# 03_TOF.net
KiCad netlist of a schematic drawn in Altium Designer
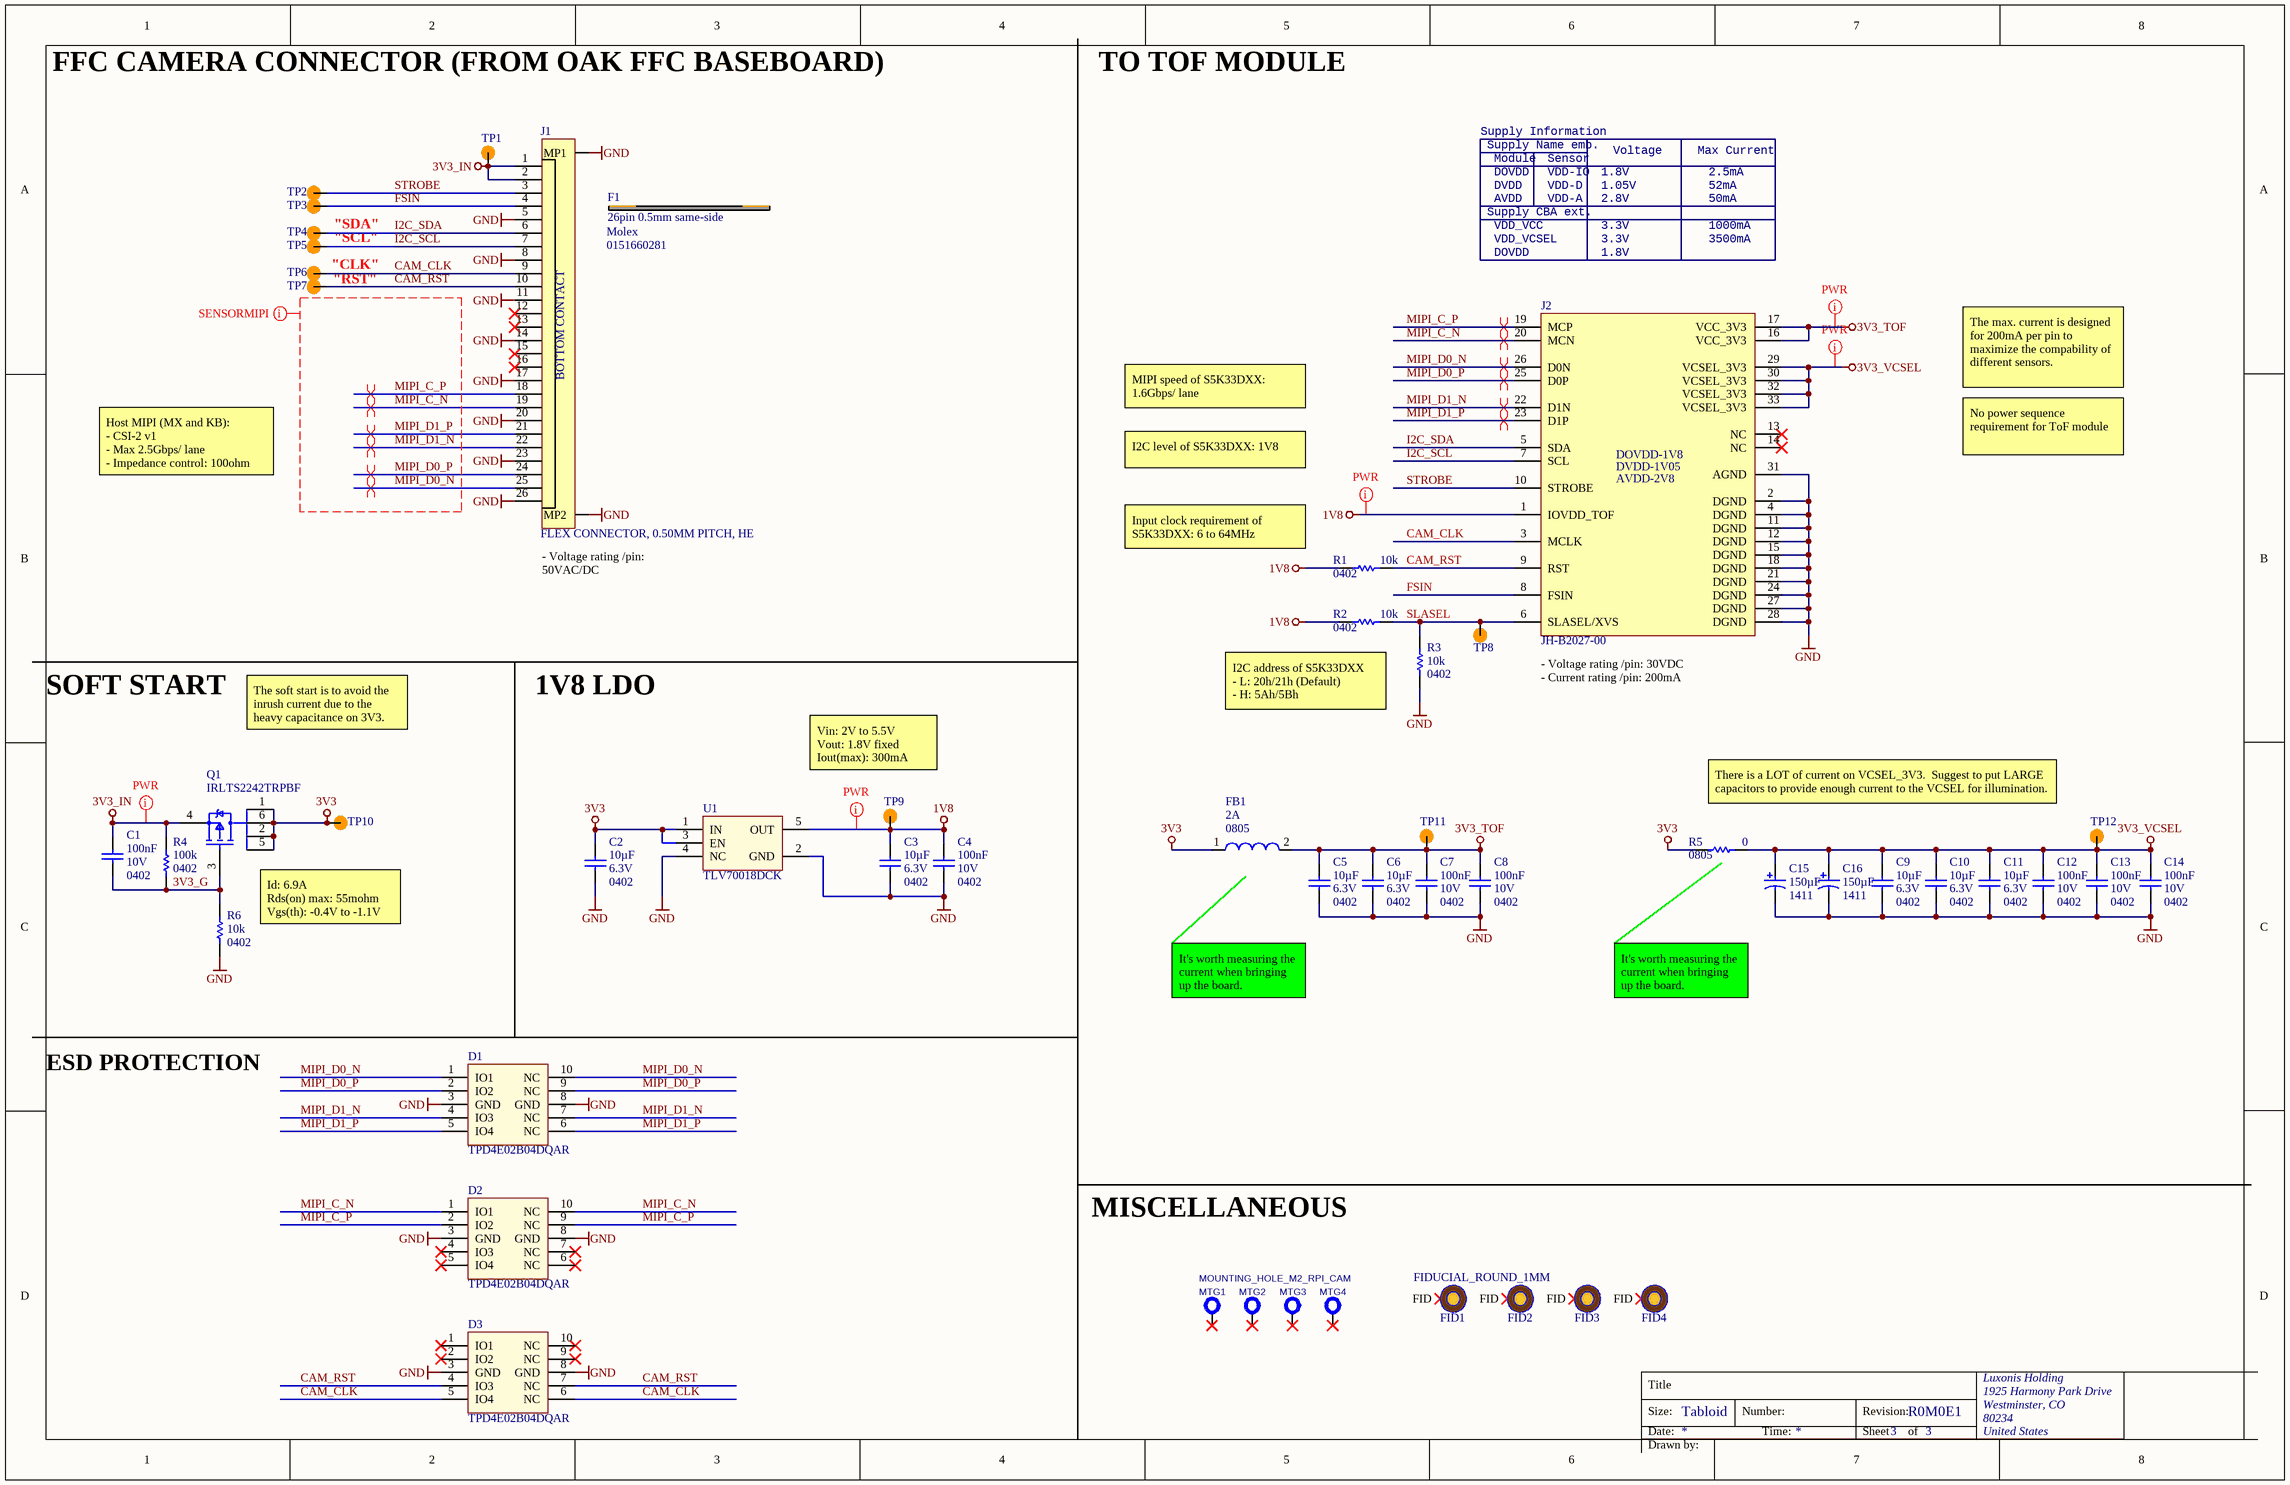
[diagram p0: 03_TOF.SchDoc]

(export (version "E")
  (design (tool "Eeschema 10.0.6"))
  (components
    (comp (ref "C1")
      (value "100nF")
      (footprint "CAPC0402(1005)70_N")
      (description "CAP CER 0.1UF 10V X7R 0402 5%")
      (fields
        (field (name "VOLTAGE RATING") "10V")
        (field (name "TOLERANCE") "5%")
        (field (name "CASE/PACKAGE") "0402")
        (field (name "Comment") "GRM155R71A104JA01D")
      )
      (libsource (lib "Luxonis LLC") (part "GRM188R61C475KAAJD"))
    )
    (comp (ref "C2")
      (value "10µF")
      (footprint "CAPC0402(1005)70_L")
      (description "CAP CER 10UF 6.3V X5R 0402 20%")
      (fields
        (field (name "CASE/PACKAGE") "0402")
        (field (name "TOLERANCE") "20%")
        (field (name "VOLTAGE RATING") "6.3V")
        (field (name "Comment") "GRM155R60J106ME15D")
      )
      (libsource (lib "Luxonis LLC") (part "LLL153C70G474ME17E"))
    )
    (comp (ref "C3")
      (value "10µF")
      (footprint "CAPC0402(1005)70_L")
      (description "CAP CER 10UF 6.3V X5R 0402 20%")
      (fields
        (field (name "CASE/PACKAGE") "0402")
        (field (name "TOLERANCE") "20%")
        (field (name "VOLTAGE RATING") "6.3V")
        (field (name "Comment") "GRM155R60J106ME15D")
      )
      (libsource (lib "Luxonis LLC") (part "LLL153C70G474ME17E"))
    )
    (comp (ref "C4")
      (value "100nF")
      (footprint "CAPC0402(1005)70_N")
      (description "CAP CER 0.1UF 10V X7R 0402 5%")
      (fields
        (field (name "VOLTAGE RATING") "10V")
        (field (name "TOLERANCE") "5%")
        (field (name "CASE/PACKAGE") "0402")
        (field (name "Comment") "GRM155R71A104JA01D")
      )
      (libsource (lib "Luxonis LLC") (part "GRM188R61C475KAAJD"))
    )
    (comp (ref "C5")
      (value "10µF")
      (footprint "CAPC0402(1005)70_L")
      (description "CAP CER 10UF 6.3V X5R 0402 20%")
      (fields
        (field (name "CASE/PACKAGE") "0402")
        (field (name "TOLERANCE") "20%")
        (field (name "VOLTAGE RATING") "6.3V")
        (field (name "Comment") "GRM155R60J106ME15D")
      )
      (libsource (lib "Luxonis LLC") (part "LLL153C70G474ME17E"))
    )
    (comp (ref "C6")
      (value "10µF")
      (footprint "CAPC0402(1005)70_L")
      (description "CAP CER 10UF 6.3V X5R 0402 20%")
      (fields
        (field (name "CASE/PACKAGE") "0402")
        (field (name "TOLERANCE") "20%")
        (field (name "VOLTAGE RATING") "6.3V")
        (field (name "Comment") "GRM155R60J106ME15D")
      )
      (libsource (lib "Luxonis LLC") (part "LLL153C70G474ME17E"))
    )
    (comp (ref "C7")
      (value "100nF")
      (footprint "CAPC0402(1005)70_N")
      (description "CAP CER 0.1UF 10V X7R 0402 5%")
      (fields
        (field (name "VOLTAGE RATING") "10V")
        (field (name "TOLERANCE") "5%")
        (field (name "CASE/PACKAGE") "0402")
        (field (name "Comment") "GRM155R71A104JA01D")
      )
      (libsource (lib "Luxonis LLC") (part "GRM188R61C475KAAJD"))
    )
    (comp (ref "C8")
      (value "100nF")
      (footprint "CAPC0402(1005)70_N")
      (description "CAP CER 0.1UF 10V X7R 0402 5%")
      (fields
        (field (name "VOLTAGE RATING") "10V")
        (field (name "TOLERANCE") "5%")
        (field (name "CASE/PACKAGE") "0402")
        (field (name "Comment") "GRM155R71A104JA01D")
      )
      (libsource (lib "Luxonis LLC") (part "GRM188R61C475KAAJD"))
    )
    (comp (ref "C9")
      (value "10µF")
      (footprint "CAPC0402(1005)70_L")
      (description "CAP CER 10UF 6.3V X5R 0402 20%")
      (fields
        (field (name "CASE/PACKAGE") "0402")
        (field (name "TOLERANCE") "20%")
        (field (name "VOLTAGE RATING") "6.3V")
        (field (name "Comment") "GRM155R60J106ME15D")
      )
      (libsource (lib "Luxonis LLC") (part "LLL153C70G474ME17E"))
    )
    (comp (ref "C10")
      (value "10µF")
      (footprint "CAPC0402(1005)70_L")
      (description "CAP CER 10UF 6.3V X5R 0402 20%")
      (fields
        (field (name "CASE/PACKAGE") "0402")
        (field (name "TOLERANCE") "20%")
        (field (name "VOLTAGE RATING") "6.3V")
        (field (name "Comment") "GRM155R60J106ME15D")
      )
      (libsource (lib "Luxonis LLC") (part "LLL153C70G474ME17E"))
    )
    (comp (ref "C11")
      (value "10µF")
      (footprint "CAPC0402(1005)70_L")
      (description "CAP CER 10UF 6.3V X5R 0402 20%")
      (fields
        (field (name "CASE/PACKAGE") "0402")
        (field (name "TOLERANCE") "20%")
        (field (name "VOLTAGE RATING") "6.3V")
        (field (name "Comment") "GRM155R60J106ME15D")
      )
      (libsource (lib "Luxonis LLC") (part "LLL153C70G474ME17E"))
    )
    (comp (ref "C12")
      (value "100nF")
      (footprint "CAPC0402(1005)70_N")
      (description "CAP CER 0.1UF 10V X7R 0402 5%")
      (fields
        (field (name "VOLTAGE RATING") "10V")
        (field (name "TOLERANCE") "5%")
        (field (name "CASE/PACKAGE") "0402")
        (field (name "Comment") "GRM155R71A104JA01D")
      )
      (libsource (lib "Luxonis LLC") (part "GRM188R61C475KAAJD"))
    )
    (comp (ref "C13")
      (value "100nF")
      (footprint "CAPC0402(1005)70_N")
      (description "CAP CER 0.1UF 10V X7R 0402 5%")
      (fields
        (field (name "VOLTAGE RATING") "10V")
        (field (name "TOLERANCE") "5%")
        (field (name "CASE/PACKAGE") "0402")
        (field (name "Comment") "GRM155R71A104JA01D")
      )
      (libsource (lib "Luxonis LLC") (part "GRM188R61C475KAAJD"))
    )
    (comp (ref "C14")
      (value "100nF")
      (footprint "CAPC0402(1005)70_N")
      (description "CAP CER 0.1UF 10V X7R 0402 5%")
      (fields
        (field (name "VOLTAGE RATING") "10V")
        (field (name "TOLERANCE") "5%")
        (field (name "CASE/PACKAGE") "0402")
        (field (name "Comment") "GRM155R71A104JA01D")
      )
      (libsource (lib "Luxonis LLC") (part "GRM188R61C475KAAJD"))
    )
    (comp (ref "C15")
      (value "150µF")
      (footprint "RESTL1210(3225)_L")
      (description "CAP TAL 150UF 10V 20%")
      (fields
        (field (name "CASE/PACKAGE") "1411")
        (field (name "TOLERANCE") "20%")
        (field (name "Comment") "TLJB157M010R0500")
      )
      (libsource (lib "Luxonis LLC") (part "TLJB157M010R0500"))
    )
    (comp (ref "C16")
      (value "150µF")
      (footprint "RESTL1210(3225)_L")
      (description "CAP TAL 150UF 10V 20%")
      (fields
        (field (name "CASE/PACKAGE") "1411")
        (field (name "TOLERANCE") "20%")
        (field (name "Comment") "TLJB157M010R0500")
      )
      (libsource (lib "Luxonis LLC") (part "TLJB157M010R0500"))
    )
    (comp (ref "D1")
      (value "TPD4E02B04DQAR")
      (footprint "TPD4E02B04DQAR")
      (libsource (lib "Luxonis LLC") (part "TPD4E02B04DQAR"))
    )
    (comp (ref "D2")
      (value "TPD4E02B04DQAR")
      (footprint "TPD4E02B04DQAR")
      (libsource (lib "Luxonis LLC") (part "TPD4E02B04DQAR"))
    )
    (comp (ref "D3")
      (value "TPD4E02B04DQAR")
      (footprint "TPD4E02B04DQAR")
      (libsource (lib "Luxonis LLC") (part "TPD4E02B04DQAR"))
    )
    (comp (ref "F1")
      (value "26pin 0.5mm same-side")
      (description "CABLE FFC 26POS 0.50MM 6\"")
      (fields
        (field (name "MANUFACTURER 1") "Molex")
        (field (name "MANUFACTURER PART NUMBER 1") "0151660281")
      )
      (libsource (lib "BG0249_R1M1E1") (part "0151660281"))
    )
    (comp (ref "FB1")
      (value "2508056017Y2")
      (footprint "2508056017Y2")
      (description "FERRITE BEAD, 0.1OHM, 2A, 0805, 600R/100MHz")
      (fields
        (field (name "CASE/PACKAGE") "0805")
        (field (name "TOLERANCE") "25%")
        (field (name "CURRENT RATING") "2A")
      )
      (libsource (lib "Luxonis LLC") (part "2508056017Y2"))
    )
    (comp (ref "FID1")
      (value "FIDUCIAL_ROUND_1MM")
      (footprint "LuxonisMaster:FIDUCIAL_ROUND_1MM")
      (description "Fiducial with various available footprints")
      (libsource (lib "LuxonisMaster") (part "FIDUCIAL"))
    )
    (comp (ref "FID2")
      (value "FIDUCIAL_ROUND_1MM")
      (footprint "LuxonisMaster:FIDUCIAL_ROUND_1MM")
      (description "Fiducial with various available footprints")
      (libsource (lib "LuxonisMaster") (part "FIDUCIAL"))
    )
    (comp (ref "FID3")
      (value "FIDUCIAL_ROUND_1MM")
      (footprint "LuxonisMaster:FIDUCIAL_ROUND_1MM")
      (description "Fiducial with various available footprints")
      (libsource (lib "LuxonisMaster") (part "FIDUCIAL"))
    )
    (comp (ref "FID4")
      (value "FIDUCIAL_ROUND_1MM")
      (footprint "LuxonisMaster:FIDUCIAL_ROUND_1MM")
      (description "Fiducial with various available footprints")
      (libsource (lib "LuxonisMaster") (part "FIDUCIAL"))
    )
    (comp (ref "J1")
      (value "FLEX CONNECTOR, 0.50MM PITCH, HE")
      (footprint "F32R-1A7H1-11026")
      (description "26 Position FFC, FPC Connector Contacts, Bottom 0.020\" (0.50mm) Surface Mount, Right Angle")
      (libsource (lib "DM1090FFC") (part "F32R-1A7H1-11026"))
    )
    (comp (ref "J2")
      (value "JH-B2027-00")
      (footprint "PCBComponent_1")
      (description "FFC/FPC Connector, 33 Contact(s), 1 Row(s), Female, Right Angle, Surface Mount Terminal")
      (libsource (lib "Luxonis LLC") (part "AC_PY004-IMX378_CON"))
    )
    (comp (ref "MTG1")
      (value "MOUNTING_HOLE_M2_RPI_CAM")
      (footprint "LuxonisMaster:MOUNTING_HOLE_M2_RPI_CAM")
      (description "=CurrentFootprint")
      (libsource (lib "LuxonisMaster") (part "MP_Mounting-Holes"))
    )
    (comp (ref "MTG2")
      (value "MOUNTING_HOLE_M2_RPI_CAM")
      (footprint "LuxonisMaster:MOUNTING_HOLE_M2_RPI_CAM")
      (description "=CurrentFootprint")
      (libsource (lib "LuxonisMaster") (part "MP_Mounting-Holes"))
    )
    (comp (ref "MTG3")
      (value "MOUNTING_HOLE_M2_RPI_CAM")
      (footprint "LuxonisMaster:MOUNTING_HOLE_M2_RPI_CAM")
      (description "=CurrentFootprint")
      (libsource (lib "LuxonisMaster") (part "MP_Mounting-Holes"))
    )
    (comp (ref "MTG4")
      (value "MOUNTING_HOLE_M2_RPI_CAM")
      (footprint "LuxonisMaster:MOUNTING_HOLE_M2_RPI_CAM")
      (description "=CurrentFootprint")
      (libsource (lib "LuxonisMaster") (part "MP_Mounting-Holes"))
    )
    (comp (ref "Q1")
      (value "IRLTS2242TRPBF")
      (footprint "TSOP-6-MFG")
      (description "MOSFET P-CH 20V 6.9A 6TSOP")
      (libsource (lib "Luxonis LLC") (part "IRLTS2242TRPBF"))
    )
    (comp (ref "R1")
      (value "10k")
      (footprint "RESC0402(1005)_N")
      (description "RES SMD 10K OHM 1% 1/16W 0402")
      (fields
        (field (name "CASE/PACKAGE") "0402")
        (field (name "TOLERANCE") "1%")
        (field (name "Comment") "RC0402FR-1310KL")
      )
      (libsource (lib "Luxonis LLC") (part "RC0402FR-0722RL_1"))
    )
    (comp (ref "R2")
      (value "10k")
      (footprint "RESC0402(1005)_N")
      (description "RES SMD 10K OHM 1% 1/16W 0402")
      (fields
        (field (name "CASE/PACKAGE") "0402")
        (field (name "TOLERANCE") "1%")
        (field (name "Comment") "RC0402FR-1310KL")
      )
      (libsource (lib "Luxonis LLC") (part "RC0402FR-0722RL_1"))
    )
    (comp (ref "R3")
      (value "10k")
      (footprint "RESC0402(1005)_N")
      (description "RES SMD 10K OHM 1% 1/16W 0402")
      (fields
        (field (name "CASE/PACKAGE") "0402")
        (field (name "TOLERANCE") "1%")
        (field (name "Comment") "RC0402FR-1310KL")
      )
      (libsource (lib "Luxonis LLC") (part "RC0402FR-0722RL_1"))
    )
    (comp (ref "R4")
      (value "100k")
      (footprint "RESC0402(1005)_L")
      (description "RES SMD 100K OHM 1% 1/16W 0402")
      (fields
        (field (name "CASE/PACKAGE") "0402")
        (field (name "TOLERANCE") "1%")
        (field (name "Comment") "RC0402FR-07100KL")
      )
      (libsource (lib "Luxonis LLC") (part "Default resistor symbol"))
    )
    (comp (ref "R5")
      (value "0")
      (footprint "RESC0805(2012)_L")
      (description "RES SMD 0 OHM 1% 1/8W 0805")
      (fields (field (name "CASE/PACKAGE") "0805") (field (name "Comment") "CRCW08050000Z0EA"))
      (libsource (lib "Luxonis LLC") (part "Default resistor symbol"))
    )
    (comp (ref "R6")
      (value "10k")
      (footprint "RESC0402(1005)_N")
      (description "RES SMD 10K OHM 1% 1/16W 0402")
      (fields
        (field (name "CASE/PACKAGE") "0402")
        (field (name "TOLERANCE") "1%")
        (field (name "Comment") "RC0402FR-1310KL")
      )
      (libsource (lib "Luxonis LLC") (part "RC0402FR-0722RL_1"))
    )
    (comp (ref "TP1")
      (value "TEST_POINT")
      (footprint "TP075_150_NS")
      (libsource (lib "Luxonis LLC") (part "TEST_POINT"))
    )
    (comp (ref "TP2")
      (value "TEST_POINT")
      (footprint "TP075_150_NS")
      (libsource (lib "Luxonis LLC") (part "TEST_POINT"))
    )
    (comp (ref "TP3")
      (value "TEST_POINT")
      (footprint "TP075_150_NS")
      (libsource (lib "Luxonis LLC") (part "TEST_POINT"))
    )
    (comp (ref "TP4")
      (value "TEST_POINT")
      (footprint "TP075_150_NS")
      (libsource (lib "Luxonis LLC") (part "TEST_POINT"))
    )
    (comp (ref "TP5")
      (value "TEST_POINT")
      (footprint "TP075_150_NS")
      (libsource (lib "Luxonis LLC") (part "TEST_POINT"))
    )
    (comp (ref "TP6")
      (value "TEST_POINT")
      (footprint "TP075_150_NS")
      (libsource (lib "Luxonis LLC") (part "TEST_POINT"))
    )
    (comp (ref "TP7")
      (value "TEST_POINT")
      (footprint "TP075_150_NS")
      (libsource (lib "Luxonis LLC") (part "TEST_POINT"))
    )
    (comp (ref "TP8")
      (value "TEST_POINT")
      (footprint "TP075_150_NS")
      (libsource (lib "Luxonis LLC") (part "TEST_POINT"))
    )
    (comp (ref "TP9")
      (value "TEST_POINT")
      (footprint "TP075_150_NS")
      (libsource (lib "Luxonis LLC") (part "TEST_POINT"))
    )
    (comp (ref "TP10")
      (value "TEST_POINT")
      (footprint "TP075_150_NS")
      (libsource (lib "Luxonis LLC") (part "TEST_POINT"))
    )
    (comp (ref "TP11")
      (value "TEST_POINT")
      (footprint "TP075_150_NS")
      (libsource (lib "Luxonis LLC") (part "TEST_POINT"))
    )
    (comp (ref "TP12")
      (value "TEST_POINT")
      (footprint "TP075_150_NS")
      (libsource (lib "Luxonis LLC") (part "TEST_POINT"))
    )
    (comp (ref "U1")
      (value "TLV70018DCK")
      (footprint "TLV70018DCK")
      (description "IC REG LINEAR 1.8V 200MA SC70-5 Linear Voltage Regulator IC  1 Output  200mA SC-70-5")
      (libsource (lib "Luxonis LLC") (part "TLV70018DCK"))
    )
  )
  (nets
    (net (code "1") (name "/3V3_G") (class "Default")
      (node (ref "C1") (pin "1") (pinfunction "1_1") (pintype "passive"))
      (node (ref "Q1") (pin "3") (pinfunction "G_3") (pintype "passive"))
      (node (ref "R4") (pin "1") (pinfunction "1_1") (pintype "passive"))
      (node (ref "R6") (pin "2") (pinfunction "2_2") (pintype "passive"))
    )
    (net (code "2") (name "/CAM_CLK") (class "Default")
      (node (ref "D3") (pin "5") (pinfunction "IO4_5") (pintype "passive"))
      (node (ref "D3") (pin "6") (pinfunction "NC_6") (pintype "passive"))
      (node (ref "J1") (pin "9") (pinfunction "9_9") (pintype "passive"))
      (node (ref "J2") (pin "3") (pinfunction "MCLK_3") (pintype "passive"))
      (node (ref "TP6") (pin "1") (pintype "passive"))
    )
    (net (code "3") (name "/CAM_RST") (class "Default")
      (node (ref "D3") (pin "4") (pinfunction "IO3_4") (pintype "passive"))
      (node (ref "D3") (pin "7") (pinfunction "NC_7") (pintype "passive"))
      (node (ref "J1") (pin "10") (pinfunction "10_10") (pintype "passive"))
      (node (ref "J2") (pin "9") (pinfunction "RST_9") (pintype "passive"))
      (node (ref "R1") (pin "2") (pinfunction "2_2") (pintype "passive"))
      (node (ref "TP7") (pin "1") (pintype "passive"))
    )
    (net (code "4") (name "/FSIN") (class "Default")
      (node (ref "J1") (pin "4") (pinfunction "4_4") (pintype "passive"))
      (node (ref "J2") (pin "8") (pinfunction "FSIN_8") (pintype "passive"))
      (node (ref "TP3") (pin "1") (pintype "passive"))
    )
    (net (code "5") (name "/I2C_SCL") (class "Default")
      (node (ref "J1") (pin "7") (pinfunction "7_7") (pintype "passive"))
      (node (ref "J2") (pin "7") (pinfunction "SCL_7") (pintype "passive"))
      (node (ref "TP5") (pin "1") (pintype "passive"))
    )
    (net (code "6") (name "/I2C_SDA") (class "Default")
      (node (ref "J1") (pin "6") (pinfunction "6_6") (pintype "passive"))
      (node (ref "J2") (pin "5") (pinfunction "SDA_5") (pintype "passive"))
      (node (ref "TP4") (pin "1") (pintype "passive"))
    )
    (net (code "7") (name "/MIPI_C_N") (class "Default")
      (node (ref "D2") (pin "1") (pinfunction "IO1_1") (pintype "passive"))
      (node (ref "D2") (pin "10") (pinfunction "NC_10") (pintype "passive"))
      (node (ref "J1") (pin "19") (pinfunction "19_19") (pintype "passive"))
      (node (ref "J2") (pin "20") (pinfunction "MCN_20") (pintype "passive"))
    )
    (net (code "8") (name "/MIPI_C_P") (class "Default")
      (node (ref "D2") (pin "2") (pinfunction "IO2_2") (pintype "passive"))
      (node (ref "D2") (pin "9") (pinfunction "NC_9") (pintype "passive"))
      (node (ref "J1") (pin "18") (pinfunction "18_18") (pintype "passive"))
      (node (ref "J2") (pin "19") (pinfunction "MCP_19") (pintype "passive"))
    )
    (net (code "9") (name "/MIPI_D0_N") (class "Default")
      (node (ref "D1") (pin "1") (pinfunction "IO1_1") (pintype "passive"))
      (node (ref "D1") (pin "10") (pinfunction "NC_10") (pintype "passive"))
      (node (ref "J1") (pin "25") (pinfunction "25_25") (pintype "passive"))
      (node (ref "J2") (pin "26") (pinfunction "D0N_26") (pintype "passive"))
    )
    (net (code "10") (name "/MIPI_D0_P") (class "Default")
      (node (ref "D1") (pin "2") (pinfunction "IO2_2") (pintype "passive"))
      (node (ref "D1") (pin "9") (pinfunction "NC_9") (pintype "passive"))
      (node (ref "J1") (pin "24") (pinfunction "24_24") (pintype "passive"))
      (node (ref "J2") (pin "25") (pinfunction "D0P_25") (pintype "passive"))
    )
    (net (code "11") (name "/MIPI_D1_N") (class "Default")
      (node (ref "D1") (pin "4") (pinfunction "IO3_4") (pintype "passive"))
      (node (ref "D1") (pin "7") (pinfunction "NC_7") (pintype "passive"))
      (node (ref "J1") (pin "22") (pinfunction "22_22") (pintype "passive"))
      (node (ref "J2") (pin "22") (pinfunction "D1N_22") (pintype "passive"))
    )
    (net (code "12") (name "/MIPI_D1_P") (class "Default")
      (node (ref "D1") (pin "5") (pinfunction "IO4_5") (pintype "passive"))
      (node (ref "D1") (pin "6") (pinfunction "NC_6") (pintype "passive"))
      (node (ref "J1") (pin "21") (pinfunction "21_21") (pintype "passive"))
      (node (ref "J2") (pin "23") (pinfunction "D1P_23") (pintype "passive"))
    )
    (net (code "13") (name "/SLASEL") (class "Default")
      (node (ref "J2") (pin "6") (pinfunction "SLASEL/XVS_6") (pintype "passive"))
      (node (ref "R2") (pin "2") (pinfunction "2_2") (pintype "passive"))
      (node (ref "R3") (pin "2") (pinfunction "2_2") (pintype "passive"))
      (node (ref "TP8") (pin "1") (pintype "passive"))
    )
    (net (code "14") (name "/STROBE") (class "Default")
      (node (ref "J1") (pin "3") (pinfunction "3_3") (pintype "passive"))
      (node (ref "J2") (pin "10") (pinfunction "STROBE_10") (pintype "passive"))
      (node (ref "TP2") (pin "1") (pintype "passive"))
    )
    (net (code "15") (name "1V8") (class "Default")
      (node (ref "C3") (pin "2") (pinfunction "2_2") (pintype "passive"))
      (node (ref "C4") (pin "2") (pinfunction "2_2") (pintype "passive"))
      (node (ref "J2") (pin "1") (pinfunction "IOVDD_TOF_1") (pintype "passive"))
      (node (ref "R1") (pin "1") (pinfunction "1_1") (pintype "passive"))
      (node (ref "R2") (pin "1") (pinfunction "1_1") (pintype "passive"))
      (node (ref "TP9") (pin "1") (pintype "passive"))
      (node (ref "U1") (pin "5") (pinfunction "OUT_5") (pintype "passive"))
    )
    (net (code "16") (name "3V3") (class "Default")
      (node (ref "C2") (pin "2") (pinfunction "2_2") (pintype "passive"))
      (node (ref "FB1") (pin "1") (pinfunction "1_1") (pintype "passive"))
      (node (ref "Q1") (pin "1") (pinfunction "D_1") (pintype "passive"))
      (node (ref "Q1") (pin "2") (pinfunction "D_2") (pintype "passive"))
      (node (ref "Q1") (pin "5") (pinfunction "D_5") (pintype "passive"))
      (node (ref "Q1") (pin "6") (pinfunction "D_6") (pintype "passive"))
      (node (ref "R5") (pin "1") (pinfunction "1_1") (pintype "passive"))
      (node (ref "TP10") (pin "1") (pintype "passive"))
      (node (ref "U1") (pin "1") (pinfunction "IN_1") (pintype "passive"))
      (node (ref "U1") (pin "3") (pinfunction "EN_3") (pintype "passive"))
    )
    (net (code "17") (name "3V3_IN") (class "Default")
      (node (ref "C1") (pin "2") (pinfunction "2_2") (pintype "passive"))
      (node (ref "J1") (pin "1") (pinfunction "1_1") (pintype "passive"))
      (node (ref "J1") (pin "2") (pinfunction "2_2") (pintype "passive"))
      (node (ref "Q1") (pin "4") (pinfunction "S_4") (pintype "passive"))
      (node (ref "R4") (pin "2") (pinfunction "2_2") (pintype "passive"))
      (node (ref "TP1") (pin "1") (pintype "passive"))
    )
    (net (code "18") (name "3V3_TOF") (class "Default")
      (node (ref "C5") (pin "2") (pinfunction "2_2") (pintype "passive"))
      (node (ref "C6") (pin "2") (pinfunction "2_2") (pintype "passive"))
      (node (ref "C7") (pin "2") (pinfunction "2_2") (pintype "passive"))
      (node (ref "C8") (pin "2") (pinfunction "2_2") (pintype "passive"))
      (node (ref "FB1") (pin "2") (pinfunction "2_2") (pintype "passive"))
      (node (ref "J2") (pin "16") (pinfunction "VCC_3V3_16") (pintype "passive"))
      (node (ref "J2") (pin "17") (pinfunction "VCC_3V3_17") (pintype "passive"))
      (node (ref "TP11") (pin "1") (pintype "passive"))
    )
    (net (code "19") (name "3V3_VCSEL") (class "Default")
      (node (ref "C10") (pin "2") (pinfunction "2_2") (pintype "passive"))
      (node (ref "C11") (pin "2") (pinfunction "2_2") (pintype "passive"))
      (node (ref "C12") (pin "2") (pinfunction "2_2") (pintype "passive"))
      (node (ref "C13") (pin "2") (pinfunction "2_2") (pintype "passive"))
      (node (ref "C14") (pin "2") (pinfunction "2_2") (pintype "passive"))
      (node (ref "C15") (pin "1") (pinfunction "1_1") (pintype "passive"))
      (node (ref "C16") (pin "1") (pinfunction "1_1") (pintype "passive"))
      (node (ref "C9") (pin "2") (pinfunction "2_2") (pintype "passive"))
      (node (ref "J2") (pin "29") (pinfunction "VCSEL_3V3_29") (pintype "passive"))
      (node (ref "J2") (pin "30") (pinfunction "VCSEL_3V3_30") (pintype "passive"))
      (node (ref "J2") (pin "32") (pinfunction "VCSEL_3V3_32") (pintype "passive"))
      (node (ref "J2") (pin "33") (pinfunction "VCSEL_3V3_33") (pintype "passive"))
      (node (ref "R5") (pin "2") (pinfunction "2_2") (pintype "passive"))
      (node (ref "TP12") (pin "1") (pintype "passive"))
    )
    (net (code "20") (name "GND") (class "Default")
      (node (ref "C10") (pin "1") (pinfunction "1_1") (pintype "passive"))
      (node (ref "C11") (pin "1") (pinfunction "1_1") (pintype "passive"))
      (node (ref "C12") (pin "1") (pinfunction "1_1") (pintype "passive"))
      (node (ref "C13") (pin "1") (pinfunction "1_1") (pintype "passive"))
      (node (ref "C14") (pin "1") (pinfunction "1_1") (pintype "passive"))
      (node (ref "C15") (pin "2") (pinfunction "2_2") (pintype "passive"))
      (node (ref "C16") (pin "2") (pinfunction "2_2") (pintype "passive"))
      (node (ref "C2") (pin "1") (pinfunction "1_1") (pintype "passive"))
      (node (ref "C3") (pin "1") (pinfunction "1_1") (pintype "passive"))
      (node (ref "C4") (pin "1") (pinfunction "1_1") (pintype "passive"))
      (node (ref "C5") (pin "1") (pinfunction "1_1") (pintype "passive"))
      (node (ref "C6") (pin "1") (pinfunction "1_1") (pintype "passive"))
      (node (ref "C7") (pin "1") (pinfunction "1_1") (pintype "passive"))
      (node (ref "C8") (pin "1") (pinfunction "1_1") (pintype "passive"))
      (node (ref "C9") (pin "1") (pinfunction "1_1") (pintype "passive"))
      (node (ref "D1") (pin "3") (pinfunction "GND_3") (pintype "passive"))
      (node (ref "D1") (pin "8") (pinfunction "GND_8") (pintype "passive"))
      (node (ref "D2") (pin "3") (pinfunction "GND_3") (pintype "passive"))
      (node (ref "D2") (pin "8") (pinfunction "GND_8") (pintype "passive"))
      (node (ref "D3") (pin "3") (pinfunction "GND_3") (pintype "passive"))
      (node (ref "D3") (pin "8") (pinfunction "GND_8") (pintype "passive"))
      (node (ref "J1") (pin "11") (pinfunction "11_11") (pintype "passive"))
      (node (ref "J1") (pin "14") (pinfunction "14_14") (pintype "passive"))
      (node (ref "J1") (pin "17") (pinfunction "17_17") (pintype "passive"))
      (node (ref "J1") (pin "20") (pinfunction "20_20") (pintype "passive"))
      (node (ref "J1") (pin "23") (pinfunction "23_23") (pintype "passive"))
      (node (ref "J1") (pin "26") (pinfunction "26_26") (pintype "passive"))
      (node (ref "J1") (pin "5") (pinfunction "5_5") (pintype "passive"))
      (node (ref "J1") (pin "8") (pinfunction "8_8") (pintype "passive"))
      (node (ref "J1") (pin "MP1") (pinfunction "MP1_MP1") (pintype "passive"))
      (node (ref "J1") (pin "MP2") (pinfunction "MP2_MP2") (pintype "passive"))
      (node (ref "J2") (pin "11") (pinfunction "DGND_11") (pintype "passive"))
      (node (ref "J2") (pin "12") (pinfunction "DGND_12") (pintype "passive"))
      (node (ref "J2") (pin "15") (pinfunction "DGND_15") (pintype "passive"))
      (node (ref "J2") (pin "18") (pinfunction "DGND_18") (pintype "passive"))
      (node (ref "J2") (pin "2") (pinfunction "DGND_2") (pintype "passive"))
      (node (ref "J2") (pin "21") (pinfunction "DGND_21") (pintype "passive"))
      (node (ref "J2") (pin "24") (pinfunction "DGND_24") (pintype "passive"))
      (node (ref "J2") (pin "27") (pinfunction "DGND_27") (pintype "passive"))
      (node (ref "J2") (pin "28") (pinfunction "DGND_28") (pintype "passive"))
      (node (ref "J2") (pin "31") (pinfunction "AGND_31") (pintype "passive"))
      (node (ref "J2") (pin "4") (pinfunction "DGND_4") (pintype "passive"))
      (node (ref "R3") (pin "1") (pinfunction "1_1") (pintype "passive"))
      (node (ref "R6") (pin "1") (pinfunction "1_1") (pintype "passive"))
      (node (ref "U1") (pin "2") (pinfunction "GND_2") (pintype "passive"))
      (node (ref "U1") (pin "4") (pinfunction "NC_4") (pintype "passive"))
    )
    (net (code "21") (name "unconnected-(D2-IO3-Pad4)") (class "Default")
      (node (ref "D2") (pin "4") (pinfunction "IO3_4") (pintype "passive+no_connect"))
    )
    (net (code "22") (name "unconnected-(D2-IO4-Pad5)") (class "Default")
      (node (ref "D2") (pin "5") (pinfunction "IO4_5") (pintype "passive+no_connect"))
    )
    (net (code "23") (name "unconnected-(D2-NC-Pad6)") (class "Default")
      (node (ref "D2") (pin "6") (pinfunction "NC_6") (pintype "passive+no_connect"))
    )
    (net (code "24") (name "unconnected-(D2-NC-Pad7)") (class "Default")
      (node (ref "D2") (pin "7") (pinfunction "NC_7") (pintype "passive+no_connect"))
    )
    (net (code "25") (name "unconnected-(D3-IO1-Pad1)") (class "Default")
      (node (ref "D3") (pin "1") (pinfunction "IO1_1") (pintype "passive+no_connect"))
    )
    (net (code "26") (name "unconnected-(D3-IO2-Pad2)") (class "Default")
      (node (ref "D3") (pin "2") (pinfunction "IO2_2") (pintype "passive+no_connect"))
    )
    (net (code "27") (name "unconnected-(D3-NC-Pad9)") (class "Default")
      (node (ref "D3") (pin "9") (pinfunction "NC_9") (pintype "passive+no_connect"))
    )
    (net (code "28") (name "unconnected-(D3-NC-Pad10)") (class "Default")
      (node (ref "D3") (pin "10") (pinfunction "NC_10") (pintype "passive+no_connect"))
    )
    (net (code "29") (name "unconnected-(FID1-PadFID)") (class "Default")
      (node (ref "FID1") (pin "FID") (pinfunction "FID_FID") (pintype "input+no_connect"))
    )
    (net (code "30") (name "unconnected-(FID2-PadFID)") (class "Default")
      (node (ref "FID2") (pin "FID") (pinfunction "FID_FID") (pintype "input+no_connect"))
    )
    (net (code "31") (name "unconnected-(FID3-PadFID)") (class "Default")
      (node (ref "FID3") (pin "FID") (pinfunction "FID_FID") (pintype "input+no_connect"))
    )
    (net (code "32") (name "unconnected-(FID4-PadFID)") (class "Default")
      (node (ref "FID4") (pin "FID") (pinfunction "FID_FID") (pintype "input+no_connect"))
    )
    (net (code "33") (name "unconnected-(J1-Pad12)") (class "Default")
      (node (ref "J1") (pin "12") (pinfunction "12_12") (pintype "passive+no_connect"))
    )
    (net (code "34") (name "unconnected-(J1-Pad13)") (class "Default")
      (node (ref "J1") (pin "13") (pinfunction "13_13") (pintype "passive+no_connect"))
    )
    (net (code "35") (name "unconnected-(J1-Pad15)") (class "Default")
      (node (ref "J1") (pin "15") (pinfunction "15_15") (pintype "passive+no_connect"))
    )
    (net (code "36") (name "unconnected-(J1-Pad16)") (class "Default")
      (node (ref "J1") (pin "16") (pinfunction "16_16") (pintype "passive+no_connect"))
    )
    (net (code "37") (name "unconnected-(J2-NC-Pad13)") (class "Default")
      (node (ref "J2") (pin "13") (pinfunction "NC_13") (pintype "passive+no_connect"))
    )
    (net (code "38") (name "unconnected-(J2-NC-Pad14)") (class "Default")
      (node (ref "J2") (pin "14") (pinfunction "NC_14") (pintype "passive+no_connect"))
    )
    (net (code "39") (name "unconnected-(MTG1-Pad1)") (class "Default")
      (node (ref "MTG1") (pin "1") (pintype "passive+no_connect"))
    )
    (net (code "40") (name "unconnected-(MTG2-Pad1)") (class "Default")
      (node (ref "MTG2") (pin "1") (pintype "passive+no_connect"))
    )
    (net (code "41") (name "unconnected-(MTG3-Pad1)") (class "Default")
      (node (ref "MTG3") (pin "1") (pintype "passive+no_connect"))
    )
    (net (code "42") (name "unconnected-(MTG4-Pad1)") (class "Default")
      (node (ref "MTG4") (pin "1") (pintype "passive+no_connect"))
    )
  )
)
